# Sheet1.net
KiCad netlist of a schematic drawn in Altium Designer
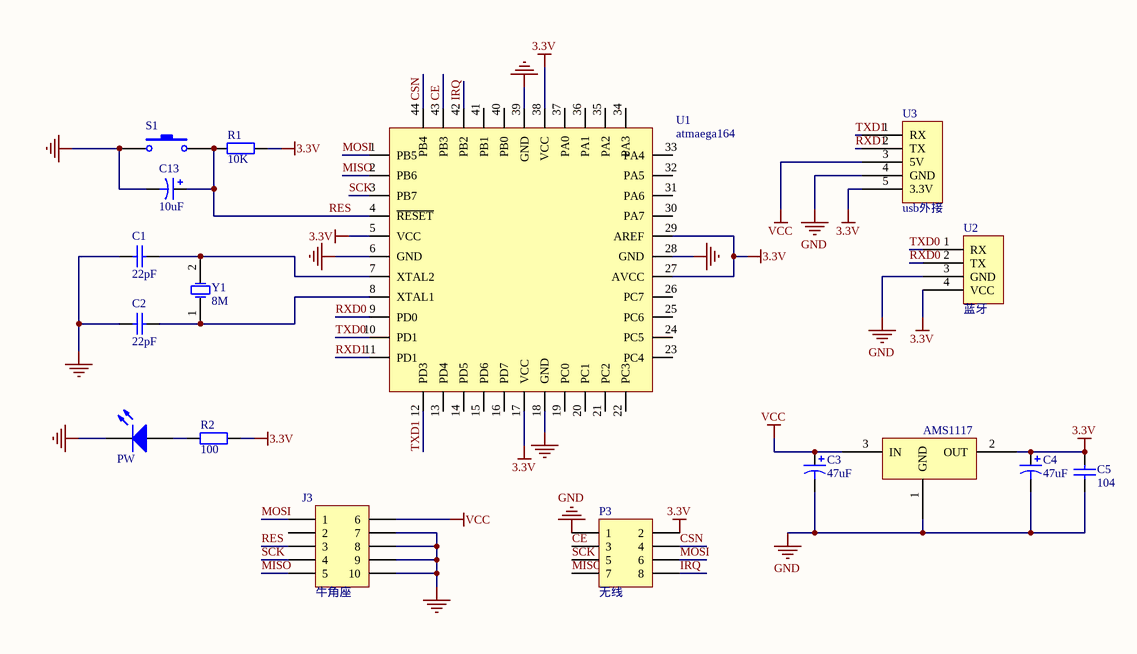
[diagram p0: Sheet1.SchDoc]

(export (version "E")
  (design (tool "Eeschema 10.0.6"))
  (components
    (comp (ref "1117_3.3V")
      (value "AMS1117")
      (footprint "AMS1117-3.3V  SOT-223  贴片")
      (libsource (lib "Schlib1") (part "Component_1"))
    )
    (comp (ref "C1")
      (value "22pF")
      (footprint "电容CBB224(0.22)")
      (description "Capacitor")
      (fields (field (name "PUBLISHER") "Altium Limited"))
      (libsource (lib "Miscellaneous Devices") (part "Cap"))
    )
    (comp (ref "C2")
      (value "22pF")
      (footprint "电容CBB224(0.22)")
      (description "Capacitor")
      (fields (field (name "PUBLISHER") "Altium Limited"))
      (libsource (lib "Miscellaneous Devices") (part "Cap"))
    )
    (comp (ref "C3")
      (value "47uF")
      (footprint "电容")
      (description "Polarized Capacitor (Surface Mount)")
      (fields (field (name "PUBLISHER") "Altium Limited"))
      (libsource (lib "") (part "Cap Pol3_1"))
    )
    (comp (ref "C4")
      (value "47uF")
      (footprint "电容")
      (description "Polarized Capacitor (Surface Mount)")
      (fields (field (name "PUBLISHER") "Altium Limited"))
      (libsource (lib "") (part "Cap Pol3_1"))
    )
    (comp (ref "C5")
      (value "104")
      (footprint "电容CBB224(0.22)")
      (description "Capacitor")
      (fields (field (name "Comment") "Cap") (field (name "PUBLISHER") "Altium Limited"))
      (libsource (lib "Miscellaneous Devices") (part "Cap"))
    )
    (comp (ref "C13")
      (value "10uF")
      (footprint "电容")
      (description "Polarized Capacitor (Surface Mount)")
      (fields (field (name "PUBLISHER") "Altium Limited"))
      (libsource (lib "Miscellaneous Devices") (part "Cap Pol3"))
    )
    (comp (ref "J3")
      (value "牛角座")
      (footprint "下载口（12345）")
      (description "Header, 5-Pin, Dual row")
      (fields (field (name "PUBLISHER") "Altium Limited"))
      (libsource (lib "Miscellaneous Connectors") (part "Header 5X2A"))
    )
    (comp (ref "P3")
      (value "无线")
      (footprint "无线模块")
      (description "Header, 4-Pin, Dual row")
      (fields (field (name "PUBLISHER") "Altium Limited"))
      (libsource (lib "Miscellaneous Connectors") (part "Header 4X2"))
    )
    (comp (ref "PW")
      (value "~")
      (footprint "LED")
      (description "Typical INFRARED GaAs LED")
      (fields (field (name "PUBLISHER") "Altium Limited"))
      (libsource (lib "Miscellaneous Devices") (part "LED0"))
    )
    (comp (ref "R1")
      (value "10K")
      (footprint "0805")
      (description "Resistor")
      (fields (field (name "PUBLISHER") "Altium Limited"))
      (libsource (lib "Miscellaneous Devices") (part "Res2"))
    )
    (comp (ref "R2")
      (value "100")
      (footprint "0805")
      (description "Resistor")
      (fields (field (name "PUBLISHER") "Altium Limited"))
      (libsource (lib "Miscellaneous Devices") (part "Res2"))
    )
    (comp (ref "S1")
      (value "~")
      (footprint "4脚按键")
      (description "Switch")
      (fields (field (name "PUBLISHER") "Altium Limited"))
      (libsource (lib "Miscellaneous Devices") (part "SW-PB"))
    )
    (comp (ref "U1")
      (value "atmaega164")
      (footprint "44贴片（顶层）")
      (libsource (lib "Schlib1") (part "atmaega164"))
    )
    (comp (ref "U2") (value "蓝牙") (footprint "蓝牙") (libsource (lib "Schlib1") (part "蓝牙")))
    (comp (ref "U3") (value "usb外接") (footprint "usb") (libsource (lib "Schlib1") (part "usb外接")))
    (comp (ref "Y1")
      (value "8M")
      (footprint "晶振")
      (description "Crystal Oscillator")
      (fields (field (name "PUBLISHER") "Altium Limited"))
      (libsource (lib "Miscellaneous Devices") (part "XTAL"))
    )
  )
  (nets
    (net (code "1") (name "/CE") (class "Default")
      (node (ref "P3") (pin "3") (pinfunction "3_3") (pintype "passive"))
      (node (ref "U1") (pin "43") (pinfunction "PB3_43") (pintype "passive"))
    )
    (net (code "2") (name "/CSN") (class "Default")
      (node (ref "P3") (pin "4") (pinfunction "4_4") (pintype "passive"))
      (node (ref "U1") (pin "44") (pinfunction "PB4_44") (pintype "passive"))
    )
    (net (code "3") (name "/IRQ") (class "Default")
      (node (ref "P3") (pin "8") (pinfunction "8_8") (pintype "passive"))
      (node (ref "U1") (pin "42") (pinfunction "PB2_42") (pintype "passive"))
    )
    (net (code "4") (name "/MISO") (class "Default")
      (node (ref "J3") (pin "5") (pinfunction "5_5") (pintype "passive"))
      (node (ref "P3") (pin "7") (pinfunction "7_7") (pintype "passive"))
      (node (ref "U1") (pin "2") (pinfunction "PB6_2") (pintype "passive"))
    )
    (net (code "5") (name "/MOSI") (class "Default")
      (node (ref "J3") (pin "1") (pinfunction "1_1") (pintype "passive"))
      (node (ref "P3") (pin "6") (pinfunction "6_6") (pintype "passive"))
      (node (ref "U1") (pin "1") (pinfunction "PB5_1") (pintype "passive"))
    )
    (net (code "6") (name "/RES") (class "Default")
      (node (ref "C13") (pin "1") (pinfunction "1_1") (pintype "passive"))
      (node (ref "J3") (pin "3") (pinfunction "3_3") (pintype "passive"))
      (node (ref "R1") (pin "2") (pinfunction "2_2") (pintype "passive"))
      (node (ref "S1") (pin "1") (pinfunction "1_1") (pintype "passive"))
      (node (ref "U1") (pin "4") (pinfunction "~{RESET}_4") (pintype "passive"))
    )
    (net (code "7") (name "/RXD0") (class "Default")
      (node (ref "U1") (pin "9") (pinfunction "PD0_9") (pintype "passive"))
      (node (ref "U2") (pin "2") (pinfunction "TX_2") (pintype "passive"))
    )
    (net (code "8") (name "/RXD1") (class "Default")
      (node (ref "U1") (pin "11") (pinfunction "PD1_11") (pintype "passive"))
      (node (ref "U3") (pin "2") (pinfunction "TX_2") (pintype "passive"))
    )
    (net (code "9") (name "/SCK") (class "Default")
      (node (ref "J3") (pin "4") (pinfunction "4_4") (pintype "passive"))
      (node (ref "P3") (pin "5") (pinfunction "5_5") (pintype "passive"))
      (node (ref "U1") (pin "3") (pinfunction "PB7_3") (pintype "passive"))
    )
    (net (code "10") (name "/TXD0") (class "Default")
      (node (ref "U1") (pin "10") (pinfunction "PD1_10") (pintype "passive"))
      (node (ref "U2") (pin "1") (pinfunction "RX_1") (pintype "passive"))
    )
    (net (code "11") (name "/TXD1") (class "Default")
      (node (ref "U1") (pin "12") (pinfunction "PD3_12") (pintype "passive"))
      (node (ref "U3") (pin "1") (pinfunction "RX_1") (pintype "passive"))
    )
    (net (code "12") (name "3.3V") (class "Default")
      (node (ref "1117_3.3V") (pin "2") (pinfunction "OUT_2") (pintype "passive"))
      (node (ref "C4") (pin "1") (pinfunction "1_1") (pintype "passive"))
      (node (ref "C5") (pin "1") (pinfunction "1_1") (pintype "passive"))
      (node (ref "P3") (pin "2") (pinfunction "2_2") (pintype "passive"))
      (node (ref "R1") (pin "1") (pinfunction "1_1") (pintype "passive"))
      (node (ref "R2") (pin "1") (pinfunction "1_1") (pintype "passive"))
      (node (ref "U1") (pin "17") (pinfunction "VCC_17") (pintype "passive"))
      (node (ref "U1") (pin "27") (pinfunction "AVCC_27") (pintype "passive"))
      (node (ref "U1") (pin "29") (pinfunction "AREF_29") (pintype "passive"))
      (node (ref "U1") (pin "38") (pinfunction "VCC_38") (pintype "passive"))
      (node (ref "U1") (pin "5") (pinfunction "VCC_5") (pintype "passive"))
      (node (ref "U2") (pin "4") (pinfunction "VCC_4") (pintype "passive"))
      (node (ref "U3") (pin "5") (pinfunction "3.3V_5") (pintype "passive"))
    )
    (net (code "13") (name "GND") (class "Default")
      (node (ref "1117_3.3V") (pin "1") (pinfunction "GND_1") (pintype "passive"))
      (node (ref "C1") (pin "1") (pinfunction "1_1") (pintype "passive"))
      (node (ref "C13") (pin "2") (pinfunction "2_2") (pintype "passive"))
      (node (ref "C2") (pin "1") (pinfunction "1_1") (pintype "passive"))
      (node (ref "C3") (pin "2") (pinfunction "2_2") (pintype "passive"))
      (node (ref "C4") (pin "2") (pinfunction "2_2") (pintype "passive"))
      (node (ref "C5") (pin "2") (pinfunction "2_2") (pintype "passive"))
      (node (ref "J3") (pin "10") (pinfunction "10_10") (pintype "passive"))
      (node (ref "J3") (pin "7") (pinfunction "7_7") (pintype "passive"))
      (node (ref "J3") (pin "8") (pinfunction "8_8") (pintype "passive"))
      (node (ref "J3") (pin "9") (pinfunction "9_9") (pintype "passive"))
      (node (ref "P3") (pin "1") (pinfunction "1_1") (pintype "passive"))
      (node (ref "PW") (pin "2") (pinfunction "K_2") (pintype "passive"))
      (node (ref "S1") (pin "2") (pinfunction "2_2") (pintype "passive"))
      (node (ref "U1") (pin "18") (pinfunction "GND_18") (pintype "passive"))
      (node (ref "U1") (pin "28") (pinfunction "GND_28") (pintype "passive"))
      (node (ref "U1") (pin "39") (pinfunction "GND_39") (pintype "passive"))
      (node (ref "U1") (pin "6") (pinfunction "GND_6") (pintype "passive"))
      (node (ref "U2") (pin "3") (pinfunction "GND_3") (pintype "passive"))
      (node (ref "U3") (pin "4") (pinfunction "GND_4") (pintype "passive"))
    )
    (net (code "14") (name "Net-(PW-A)") (class "Default")
      (node (ref "PW") (pin "1") (pinfunction "A_1") (pintype "passive"))
      (node (ref "R2") (pin "2") (pinfunction "2_2") (pintype "passive"))
    )
    (net (code "15") (name "Net-(U1-XTAL1)") (class "Default")
      (node (ref "C2") (pin "2") (pinfunction "2_2") (pintype "passive"))
      (node (ref "U1") (pin "8") (pinfunction "XTAL1_8") (pintype "passive"))
      (node (ref "Y1") (pin "1") (pinfunction "OSC1_1") (pintype "passive"))
    )
    (net (code "16") (name "Net-(U1-XTAL2)") (class "Default")
      (node (ref "C1") (pin "2") (pinfunction "2_2") (pintype "passive"))
      (node (ref "U1") (pin "7") (pinfunction "XTAL2_7") (pintype "passive"))
      (node (ref "Y1") (pin "2") (pinfunction "OSC2_2") (pintype "passive"))
    )
    (net (code "17") (name "VCC") (class "Default")
      (node (ref "1117_3.3V") (pin "3") (pinfunction "IN_3") (pintype "passive"))
      (node (ref "C3") (pin "1") (pinfunction "1_1") (pintype "passive"))
      (node (ref "J3") (pin "6") (pinfunction "6_6") (pintype "passive"))
      (node (ref "U3") (pin "3") (pinfunction "5V_3") (pintype "passive"))
    )
    (net (code "18") (name "unconnected-(J3-Pad2)") (class "Default")
      (node (ref "J3") (pin "2") (pinfunction "2_2") (pintype "passive"))
    )
    (net (code "19") (name "unconnected-(U1-PA0-Pad37)") (class "Default")
      (node (ref "U1") (pin "37") (pinfunction "PA0_37") (pintype "passive"))
    )
    (net (code "20") (name "unconnected-(U1-PA1-Pad36)") (class "Default")
      (node (ref "U1") (pin "36") (pinfunction "PA1_36") (pintype "passive"))
    )
    (net (code "21") (name "unconnected-(U1-PA2-Pad35)") (class "Default")
      (node (ref "U1") (pin "35") (pinfunction "PA2_35") (pintype "passive"))
    )
    (net (code "22") (name "unconnected-(U1-PA3-Pad34)") (class "Default")
      (node (ref "U1") (pin "34") (pinfunction "PA3_34") (pintype "passive"))
    )
    (net (code "23") (name "unconnected-(U1-PA4-Pad33)") (class "Default")
      (node (ref "U1") (pin "33") (pinfunction "PA4_33") (pintype "passive"))
    )
    (net (code "24") (name "unconnected-(U1-PA5-Pad32)") (class "Default")
      (node (ref "U1") (pin "32") (pinfunction "PA5_32") (pintype "passive"))
    )
    (net (code "25") (name "unconnected-(U1-PA6-Pad31)") (class "Default")
      (node (ref "U1") (pin "31") (pinfunction "PA6_31") (pintype "passive"))
    )
    (net (code "26") (name "unconnected-(U1-PA7-Pad30)") (class "Default")
      (node (ref "U1") (pin "30") (pinfunction "PA7_30") (pintype "passive"))
    )
    (net (code "27") (name "unconnected-(U1-PB0-Pad40)") (class "Default")
      (node (ref "U1") (pin "40") (pinfunction "PB0_40") (pintype "passive"))
    )
    (net (code "28") (name "unconnected-(U1-PB1-Pad41)") (class "Default")
      (node (ref "U1") (pin "41") (pinfunction "PB1_41") (pintype "passive"))
    )
    (net (code "29") (name "unconnected-(U1-PC0-Pad19)") (class "Default")
      (node (ref "U1") (pin "19") (pinfunction "PC0_19") (pintype "passive"))
    )
    (net (code "30") (name "unconnected-(U1-PC1-Pad20)") (class "Default")
      (node (ref "U1") (pin "20") (pinfunction "PC1_20") (pintype "passive"))
    )
    (net (code "31") (name "unconnected-(U1-PC2-Pad21)") (class "Default")
      (node (ref "U1") (pin "21") (pinfunction "PC2_21") (pintype "passive"))
    )
    (net (code "32") (name "unconnected-(U1-PC3-Pad22)") (class "Default")
      (node (ref "U1") (pin "22") (pinfunction "PC3_22") (pintype "passive"))
    )
    (net (code "33") (name "unconnected-(U1-PC4-Pad23)") (class "Default")
      (node (ref "U1") (pin "23") (pinfunction "PC4_23") (pintype "passive"))
    )
    (net (code "34") (name "unconnected-(U1-PC5-Pad24)") (class "Default")
      (node (ref "U1") (pin "24") (pinfunction "PC5_24") (pintype "passive"))
    )
    (net (code "35") (name "unconnected-(U1-PC6-Pad25)") (class "Default")
      (node (ref "U1") (pin "25") (pinfunction "PC6_25") (pintype "passive"))
    )
    (net (code "36") (name "unconnected-(U1-PC7-Pad26)") (class "Default")
      (node (ref "U1") (pin "26") (pinfunction "PC7_26") (pintype "passive"))
    )
    (net (code "37") (name "unconnected-(U1-PD4-Pad13)") (class "Default")
      (node (ref "U1") (pin "13") (pinfunction "PD4_13") (pintype "passive"))
    )
    (net (code "38") (name "unconnected-(U1-PD5-Pad14)") (class "Default")
      (node (ref "U1") (pin "14") (pinfunction "PD5_14") (pintype "passive"))
    )
    (net (code "39") (name "unconnected-(U1-PD6-Pad15)") (class "Default")
      (node (ref "U1") (pin "15") (pinfunction "PD6_15") (pintype "passive"))
    )
    (net (code "40") (name "unconnected-(U1-PD7-Pad16)") (class "Default")
      (node (ref "U1") (pin "16") (pinfunction "PD7_16") (pintype "passive"))
    )
  )
)
